# design.net
KiCad netlist of a schematic drawn in Altium Designer
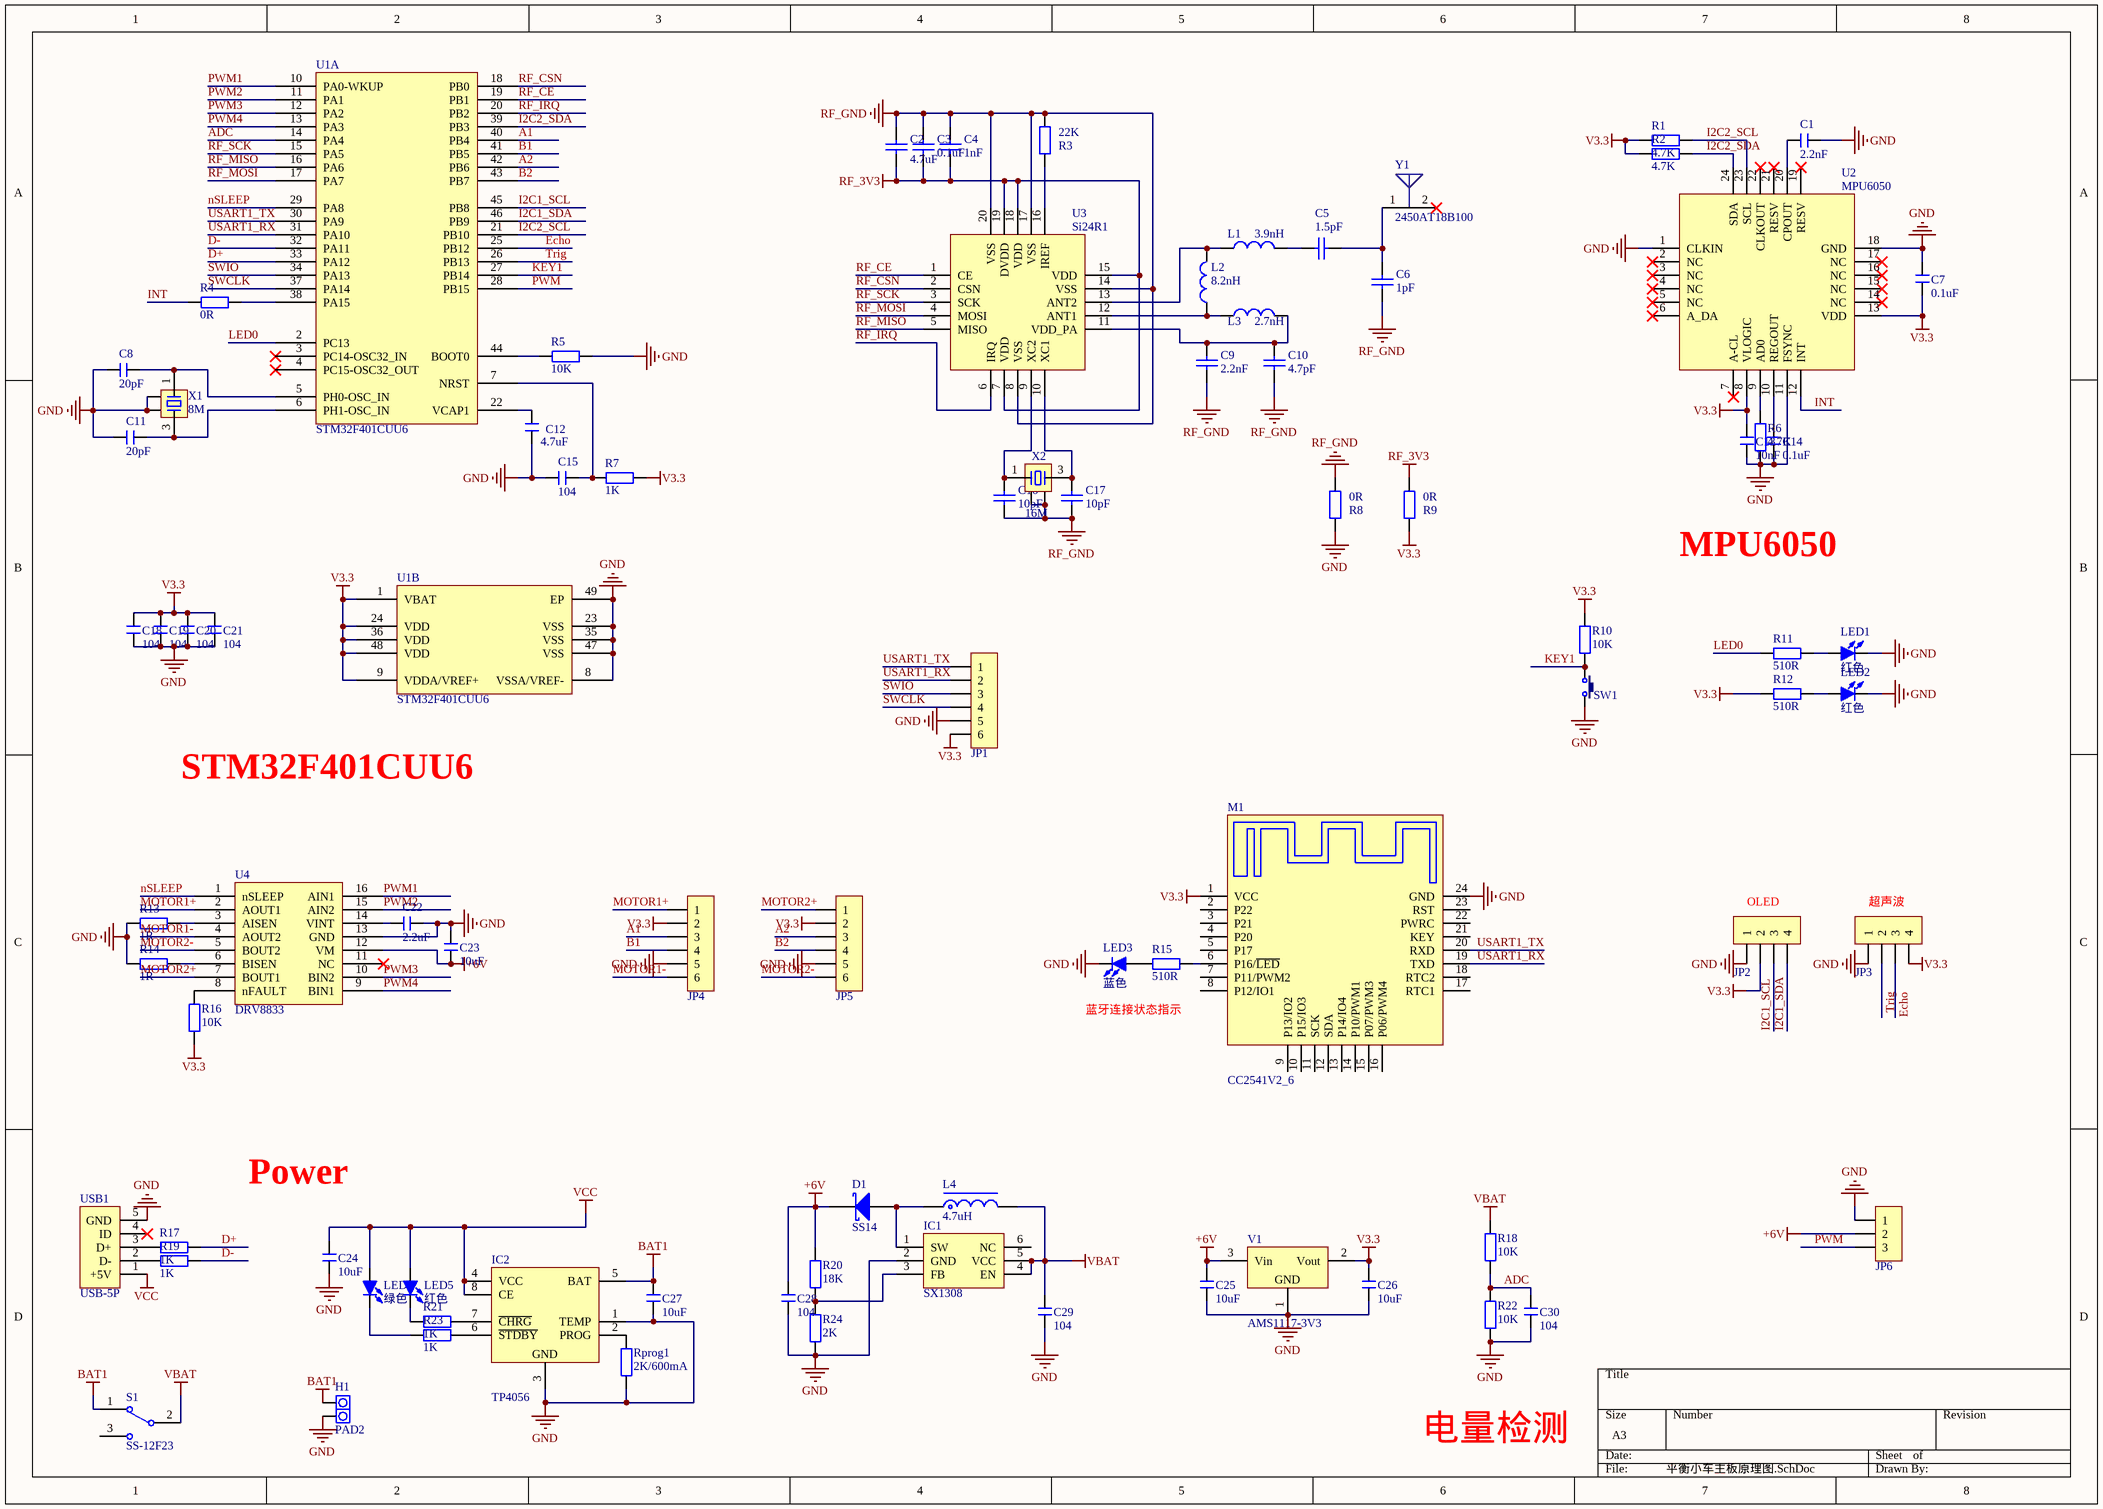
[diagram p0: 平衡小车主板原理图.SchDoc]

(export (version "E")
  (design (tool "Eeschema 10.0.6"))
  (components
    (comp (ref "C1")
      (value "2.2nF")
      (footprint "C 0603_L")
      (description "贴片电容")
      (libsource (lib "0.1 - 电阻-电容-电感") (part "C"))
    )
    (comp (ref "C2")
      (value "4.7uF")
      (footprint "C 0603_L")
      (fields (field (name "Comment") "C_0603") (field (name "PUBLISHER") "Altium Limited"))
      (libsource (lib "RoboFly") (part "C_0603"))
    )
    (comp (ref "C3")
      (value "0.1uF")
      (footprint "C 0603_L")
      (fields (field (name "Comment") "C_0603") (field (name "PUBLISHER") "Altium Limited"))
      (libsource (lib "RoboFly") (part "C_0603"))
    )
    (comp (ref "C4")
      (value "1nF")
      (footprint "C 0603_L")
      (fields (field (name "Comment") "C_0603") (field (name "PUBLISHER") "Altium Limited"))
      (libsource (lib "RoboFly") (part "C_0603"))
    )
    (comp (ref "C5")
      (value "1.5pF")
      (footprint "C 0603_L")
      (fields (field (name "Comment") "C_0603") (field (name "PUBLISHER") "Altium Limited"))
      (libsource (lib "RoboFly") (part "C_0603"))
    )
    (comp (ref "C6")
      (value "1pF")
      (footprint "C 0603_L")
      (fields (field (name "Comment") "C_0603") (field (name "PUBLISHER") "Altium Limited"))
      (libsource (lib "RoboFly") (part "C_0603"))
    )
    (comp (ref "C7")
      (value "0.1uF")
      (footprint "C 0603_L")
      (description "贴片电容")
      (libsource (lib "0.1 - 电阻-电容-电感") (part "C"))
    )
    (comp (ref "C8")
      (value "20pF")
      (footprint "R 0603_M")
      (description "贴片电容")
      (libsource (lib "0.1 - 电阻-电容-电感") (part "C"))
    )
    (comp (ref "C9")
      (value "2.2nF")
      (footprint "C 0603_L")
      (fields (field (name "Comment") "C_0603") (field (name "PUBLISHER") "Altium Limited"))
      (libsource (lib "RoboFly") (part "C_0603"))
    )
    (comp (ref "C10")
      (value "4.7pF")
      (footprint "C 0603_L")
      (fields (field (name "Comment") "C_0603") (field (name "PUBLISHER") "Altium Limited"))
      (libsource (lib "RoboFly") (part "C_0603"))
    )
    (comp (ref "C11")
      (value "20pF")
      (footprint "R 0603_M")
      (description "贴片电容")
      (libsource (lib "0.1 - 电阻-电容-电感") (part "C"))
    )
    (comp (ref "C12")
      (value "4.7uF")
      (footprint "C 0603_L")
      (description "贴片电容")
      (libsource (lib "0.1 - 电阻-电容-电感") (part "C"))
    )
    (comp (ref "C13")
      (value "10nF")
      (footprint "C 0603_L")
      (description "贴片电容")
      (libsource (lib "0.1 - 电阻-电容-电感") (part "C"))
    )
    (comp (ref "C14")
      (value "0.1uF")
      (footprint "C 0603_L")
      (description "贴片电容")
      (libsource (lib "0.1 - 电阻-电容-电感") (part "C"))
    )
    (comp (ref "C15")
      (value "104")
      (footprint "C 0603_L")
      (description "贴片电容")
      (libsource (lib "0.1 - 电阻-电容-电感") (part "C"))
    )
    (comp (ref "C16")
      (value "10pF")
      (footprint "C 0603_L")
      (fields (field (name "Comment") "C_0603") (field (name "PUBLISHER") "Altium Limited"))
      (libsource (lib "RoboFly") (part "C_0603"))
    )
    (comp (ref "C17")
      (value "10pF")
      (footprint "C 0603_L")
      (fields (field (name "Comment") "C_0603") (field (name "PUBLISHER") "Altium Limited"))
      (libsource (lib "RoboFly") (part "C_0603"))
    )
    (comp (ref "C18")
      (value "104")
      (footprint "C 0603_L")
      (description "贴片电容")
      (libsource (lib "0.1 - 电阻-电容-电感") (part "C"))
    )
    (comp (ref "C19")
      (value "104")
      (footprint "C 0603_L")
      (description "贴片电容")
      (libsource (lib "0.1 - 电阻-电容-电感") (part "C"))
    )
    (comp (ref "C20")
      (value "104")
      (footprint "C 0603_L")
      (description "贴片电容")
      (libsource (lib "0.1 - 电阻-电容-电感") (part "C"))
    )
    (comp (ref "C21")
      (value "104")
      (footprint "C 0603_L")
      (description "贴片电容")
      (libsource (lib "0.1 - 电阻-电容-电感") (part "C"))
    )
    (comp (ref "C22")
      (value "2.2uF")
      (footprint "C 0603_L")
      (description "贴片电容")
      (libsource (lib "0.1 - 电阻-电容-电感") (part "C"))
    )
    (comp (ref "C23")
      (value "10uF")
      (footprint "C 0603_L")
      (description "贴片电容")
      (libsource (lib "0.1 - 电阻-电容-电感") (part "C"))
    )
    (comp (ref "C24")
      (value "10uF")
      (footprint "C 0603_L")
      (description "贴片电容")
      (libsource (lib "0.1 - 电阻-电容-电感") (part "C"))
    )
    (comp (ref "C25")
      (value "10uF")
      (footprint "C 0603_L")
      (description "贴片电容")
      (libsource (lib "0.1 - 电阻-电容-电感") (part "C"))
    )
    (comp (ref "C26")
      (value "10uF")
      (footprint "C 0603_L")
      (description "贴片电容")
      (libsource (lib "0.1 - 电阻-电容-电感") (part "C"))
    )
    (comp (ref "C27")
      (value "10uF")
      (footprint "C 0603_L")
      (description "贴片电容")
      (libsource (lib "0.1 - 电阻-电容-电感") (part "C"))
    )
    (comp (ref "C28")
      (value "104")
      (footprint "C 0603_L")
      (description "贴片电容")
      (libsource (lib "0.1 - 电阻-电容-电感") (part "C"))
    )
    (comp (ref "C29")
      (value "104")
      (footprint "C 0603_L")
      (description "贴片电容")
      (libsource (lib "0.1 - 电阻-电容-电感") (part "C"))
    )
    (comp (ref "C30")
      (value "104")
      (footprint "C 0603_L")
      (description "贴片电容")
      (libsource (lib "0.1 - 电阻-电容-电感") (part "C"))
    )
    (comp (ref "D1")
      (value "SS14")
      (footprint "SMA")
      (description "肖特基二极管")
      (libsource (lib "0.2 -  二极管-整流桥") (part "SS14"))
    )
    (comp (ref "H1")
      (value "PAD2")
      (footprint "PAD2-2.54")
      (description "引线焊盘")
      (fields (field (name "版权归属") "封装库来自淘宝 ID：黄晶宝石"))
      (libsource (lib "4.1 - 未分类器件") (part "PAD2"))
    )
    (comp (ref "IC1")
      (value "SX1308")
      (footprint "SOT23-6N")
      (description "可调升压芯片")
      (fields (field (name "版权归属") "封装库来自淘宝 ID：黄晶宝石"))
      (libsource (lib "1.1 - 电源类芯片") (part "SX1308"))
    )
    (comp (ref "IC2")
      (value "TP4056")
      (footprint "SOP8_N")
      (description "锂电池充电管理")
      (libsource (lib "1.1 - 电源类芯片") (part "TP4056"))
    )
    (comp (ref "JP1")
      (value "HDR-1X6")
      (footprint "SH1.0-6P")
      (description "6P接插件")
      (fields (field (name "版权归属") "封装库来自淘宝 ID：黄晶宝石"))
      (libsource (lib "5.3 - 接插件-脚距2.54 (100mil) ") (part "Header 6"))
    )
    (comp (ref "JP2")
      (value "HDR-1X4")
      (footprint "HDR2.54-M-LI-4P")
      (description "4P接插件")
      (fields (field (name "版权归属") "封装库来自淘宝 ID：黄晶宝石"))
      (libsource (lib "5.3 - 接插件-脚距2.54 (100mil) ") (part "Header 4"))
    )
    (comp (ref "JP3")
      (value "HDR-1X4")
      (footprint "HDR2.54-M-LI-4P")
      (description "4P接插件")
      (fields (field (name "版权归属") "封装库来自淘宝 ID：黄晶宝石"))
      (libsource (lib "5.3 - 接插件-脚距2.54 (100mil) ") (part "Header 4"))
    )
    (comp (ref "JP4")
      (value "HDR-1X6")
      (footprint "SH1.0-6P")
      (description "6P接插件")
      (fields (field (name "版权归属") "封装库来自淘宝 ID：黄晶宝石"))
      (libsource (lib "5.3 - 接插件-脚距2.54 (100mil) ") (part "Header 6"))
    )
    (comp (ref "JP5")
      (value "HDR-1X6")
      (footprint "SH1.0-6P")
      (description "6P接插件")
      (fields (field (name "版权归属") "封装库来自淘宝 ID：黄晶宝石"))
      (libsource (lib "5.3 - 接插件-脚距2.54 (100mil) ") (part "Header 6"))
    )
    (comp (ref "JP6")
      (value "HDR-1X3")
      (footprint "HDR2.54-LI-3P")
      (description "3P接插件")
      (fields (field (name "版权归属") "封装库来自淘宝 ID：黄晶宝石"))
      (libsource (lib "5.3 - 接插件-脚距2.54 (100mil) ") (part "Header 3"))
    )
    (comp (ref "L1")
      (value "3.9nH")
      (footprint "L 0603")
      (description "电感")
      (fields (field (name "Comment") "Inductor") (field (name "PUBLISHER") "Altium Limited"))
      (libsource (lib "RoboFly") (part "Inductor_1"))
    )
    (comp (ref "L2")
      (value "8.2nH")
      (footprint "L 0603")
      (description "电感")
      (fields (field (name "Comment") "Inductor") (field (name "PUBLISHER") "Altium Limited"))
      (libsource (lib "RoboFly") (part "Inductor_1"))
    )
    (comp (ref "L3")
      (value "2.7nH")
      (footprint "L 0603")
      (description "电感")
      (fields (field (name "Comment") "Inductor") (field (name "PUBLISHER") "Altium Limited"))
      (libsource (lib "RoboFly") (part "Inductor_1"))
    )
    (comp (ref "L4")
      (value "4.7uH")
      (footprint "NR4020")
      (description "NR磁胶电感")
      (fields (field (name "版权归属") "来自淘宝 ID：黄晶宝石"))
      (libsource (lib "0.1 - 电阻-电容-电感") (part "L-NR"))
    )
    (comp (ref "LED1")
      (value "红色")
      (footprint "LED 0603R")
      (description "贴片LED")
      (fields (field (name "版权归属") "封装库来自淘宝 ID：黄晶宝石"))
      (libsource (lib "0.3 - LED发光二极管") (part "LED-SMD"))
    )
    (comp (ref "LED2")
      (value "红色")
      (footprint "LED 0603R")
      (description "贴片LED")
      (fields (field (name "版权归属") "封装库来自淘宝 ID：黄晶宝石"))
      (libsource (lib "0.3 - LED发光二极管") (part "LED-SMD"))
    )
    (comp (ref "LED3")
      (value "蓝色")
      (footprint "LED 0603B")
      (description "贴片LED")
      (fields (field (name "版权归属") "封装库来自淘宝 ID：黄晶宝石"))
      (libsource (lib "0.3 - LED发光二极管") (part "LED-SMD"))
    )
    (comp (ref "LED4")
      (value "绿色")
      (footprint "LED 0603G")
      (description "贴片LED")
      (fields (field (name "版权归属") "封装库来自淘宝 ID：黄晶宝石"))
      (libsource (lib "0.3 - LED发光二极管") (part "LED-SMD"))
    )
    (comp (ref "LED5")
      (value "红色")
      (footprint "LED 0603R")
      (description "贴片LED")
      (fields (field (name "版权归属") "封装库来自淘宝 ID：黄晶宝石"))
      (libsource (lib "0.3 - LED发光二极管") (part "LED-SMD"))
    )
    (comp (ref "M1")
      (value "CC2541V2_6")
      (footprint "CC2541V2_6")
      (description "蓝牙4.0透传模块")
      (fields (field (name "版权归属") "封装库来自淘宝 ID：黄晶宝石"))
      (libsource (lib "0.9 - 模块") (part "CC2541V2_6"))
    )
    (comp (ref "R1")
      (value "4.7K")
      (footprint "R 0603_L")
      (description "贴片电阻")
      (fields (field (name "版权归属") "来自淘宝 ID：黄晶宝石"))
      (libsource (lib "0.1 - 电阻-电容-电感") (part "R"))
    )
    (comp (ref "R2")
      (value "4.7K")
      (footprint "R 0603_L")
      (description "贴片电阻")
      (fields (field (name "版权归属") "来自淘宝 ID：黄晶宝石"))
      (libsource (lib "0.1 - 电阻-电容-电感") (part "R"))
    )
    (comp (ref "R3")
      (value "22K")
      (footprint "R 0603_L")
      (fields (field (name "Comment") "R_0603") (field (name "PUBLISHER") "Altium Limited"))
      (libsource (lib "RoboFly") (part "R_0603"))
    )
    (comp (ref "R4")
      (value "0R")
      (footprint "R 0603_L")
      (description "贴片电阻")
      (fields (field (name "版权归属") "来自淘宝 ID：黄晶宝石"))
      (libsource (lib "0.1 - 电阻-电容-电感") (part "R"))
    )
    (comp (ref "R5")
      (value "10K")
      (footprint "R 0603_L")
      (description "贴片电阻")
      (fields (field (name "版权归属") "来自淘宝 ID：黄晶宝石"))
      (libsource (lib "0.1 - 电阻-电容-电感") (part "R"))
    )
    (comp (ref "R6")
      (value "4.7K")
      (footprint "R 0603_L")
      (description "贴片电阻")
      (fields (field (name "版权归属") "来自淘宝 ID：黄晶宝石"))
      (libsource (lib "0.1 - 电阻-电容-电感") (part "R"))
    )
    (comp (ref "R7")
      (value "1K")
      (footprint "R 0603_L")
      (description "贴片电阻")
      (fields (field (name "版权归属") "来自淘宝 ID：黄晶宝石"))
      (libsource (lib "0.1 - 电阻-电容-电感") (part "R"))
    )
    (comp (ref "R8")
      (value "0R")
      (footprint "R 0603_L")
      (fields (field (name "Comment") "R_0603") (field (name "PUBLISHER") "Altium Limited"))
      (libsource (lib "RoboFly") (part "R_0603"))
    )
    (comp (ref "R9")
      (value "0R")
      (footprint "R 0603_L")
      (fields (field (name "Comment") "R_0603") (field (name "PUBLISHER") "Altium Limited"))
      (libsource (lib "RoboFly") (part "R_0603"))
    )
    (comp (ref "R10")
      (value "10K")
      (footprint "R 0603_L")
      (description "贴片电阻")
      (fields (field (name "版权归属") "来自淘宝 ID：黄晶宝石"))
      (libsource (lib "0.1 - 电阻-电容-电感") (part "R"))
    )
    (comp (ref "R11")
      (value "510R")
      (footprint "R 0603_L")
      (description "贴片电阻")
      (fields (field (name "版权归属") "来自淘宝 ID：黄晶宝石"))
      (libsource (lib "0.1 - 电阻-电容-电感") (part "R"))
    )
    (comp (ref "R12")
      (value "510R")
      (footprint "R 0603_L")
      (description "贴片电阻")
      (fields (field (name "版权归属") "来自淘宝 ID：黄晶宝石"))
      (libsource (lib "0.1 - 电阻-电容-电感") (part "R"))
    )
    (comp (ref "R13")
      (value "1R")
      (footprint "R 0603_L")
      (description "贴片电阻")
      (fields (field (name "版权归属") "来自淘宝 ID：黄晶宝石"))
      (libsource (lib "0.1 - 电阻-电容-电感") (part "R"))
    )
    (comp (ref "R14")
      (value "1R")
      (footprint "R 0603_L")
      (description "贴片电阻")
      (fields (field (name "版权归属") "来自淘宝 ID：黄晶宝石"))
      (libsource (lib "0.1 - 电阻-电容-电感") (part "R"))
    )
    (comp (ref "R15")
      (value "510R")
      (footprint "R 0603_L")
      (description "贴片电阻")
      (fields (field (name "版权归属") "来自淘宝 ID：黄晶宝石"))
      (libsource (lib "0.1 - 电阻-电容-电感") (part "R"))
    )
    (comp (ref "R16")
      (value "10K")
      (footprint "R 0603_L")
      (description "贴片电阻")
      (fields (field (name "版权归属") "来自淘宝 ID：黄晶宝石"))
      (libsource (lib "0.1 - 电阻-电容-电感") (part "R"))
    )
    (comp (ref "R17")
      (value "1K")
      (footprint "R 0603_L")
      (description "贴片电阻")
      (fields (field (name "版权归属") "来自淘宝 ID：黄晶宝石"))
      (libsource (lib "0.1 - 电阻-电容-电感") (part "R"))
    )
    (comp (ref "R18")
      (value "10K")
      (footprint "R 0603_L")
      (description "贴片电阻")
      (fields (field (name "版权归属") "来自淘宝 ID：黄晶宝石"))
      (libsource (lib "0.1 - 电阻-电容-电感") (part "R"))
    )
    (comp (ref "R19")
      (value "1K")
      (footprint "R 0603_L")
      (description "贴片电阻")
      (fields (field (name "版权归属") "来自淘宝 ID：黄晶宝石"))
      (libsource (lib "0.1 - 电阻-电容-电感") (part "R"))
    )
    (comp (ref "R20")
      (value "18K")
      (footprint "R 0603_L")
      (description "贴片电阻")
      (fields (field (name "版权归属") "来自淘宝 ID：黄晶宝石"))
      (libsource (lib "0.1 - 电阻-电容-电感") (part "R"))
    )
    (comp (ref "R21")
      (value "1K")
      (footprint "R 0603_L")
      (description "贴片电阻")
      (fields (field (name "版权归属") "来自淘宝 ID：黄晶宝石"))
      (libsource (lib "0.1 - 电阻-电容-电感") (part "R"))
    )
    (comp (ref "R22")
      (value "10K")
      (footprint "R 0603_L")
      (description "贴片电阻")
      (fields (field (name "版权归属") "来自淘宝 ID：黄晶宝石"))
      (libsource (lib "0.1 - 电阻-电容-电感") (part "R"))
    )
    (comp (ref "R23")
      (value "1K")
      (footprint "R 0603_L")
      (description "贴片电阻")
      (fields (field (name "版权归属") "来自淘宝 ID：黄晶宝石"))
      (libsource (lib "0.1 - 电阻-电容-电感") (part "R"))
    )
    (comp (ref "R24")
      (value "2K")
      (footprint "R 0603_L")
      (description "贴片电阻")
      (fields (field (name "版权归属") "来自淘宝 ID：黄晶宝石"))
      (libsource (lib "0.1 - 电阻-电容-电感") (part "R"))
    )
    (comp (ref "Rprog1")
      (value "2K/600mA")
      (footprint "R 0603_M")
      (description "贴片电阻")
      (fields (field (name "版权归属") "来自淘宝 ID：黄晶宝石"))
      (libsource (lib "0.1 - 电阻-电容-电感") (part "R"))
    )
    (comp (ref "S1")
      (value "SS-12F23")
      (footprint "SWITCH_PWR")
      (description "1路波动开关")
      (fields (field (name "版权归属") "封装库来自淘宝 ID：黄晶宝石"))
      (libsource (lib "0.7 - 常用按键-开关") (part "SSW-1P"))
    )
    (comp (ref "SW1")
      (value "3x6x5")
      (footprint "TSW SMD-3*6*2.5")
      (description "3x6轻触开关")
      (fields (field (name "版权归属") "封装库来自淘宝 ID：黄晶宝石"))
      (libsource (lib "0.7 - 常用按键-开关") (part "TSW 3x6"))
    )
    (comp (ref "U1")
      (value "STM32F401CUU6")
      (footprint "QFN48 7X7_M")
      (libsource (lib "Schlib1") (part "STM32F401CUU6"))
    )
    (comp (ref "U2") (value "MPU6050") (footprint "QFN24 4x4_M") (libsource (lib "RoboFly") (part "MPU6050")))
    (comp (ref "U3") (value "Si24R1") (footprint "QFN20 4x4_M") (libsource (lib "RoboFly") (part "nRF24L01")))
    (comp (ref "U4")
      (value "DRV8833")
      (footprint "TSSOP-16")
      (description "DRV8833电机驱动芯片2.7v-10.8v")
      (libsource (lib "原理图库") (part "DRV8833"))
    )
    (comp (ref "USB1")
      (value "USB-5P")
      (footprint "USB-MICRO_D")
      (description "微型USB母座")
      (libsource (lib "0.8 - 网口-音频插座") (part "USB-5P"))
    )
    (comp (ref "V1")
      (value "AMS1117-3V3")
      (footprint "SOT223_L")
      (description "三端稳压芯片")
      (libsource (lib "1.1 - 电源类芯片") (part "AMS1117"))
    )
    (comp (ref "X1")
      (value "8M")
      (footprint "OSC 3225-4P")
      (description "4脚无源晶振")
      (fields (field (name "版权归属") "源创客"))
      (libsource (lib "") (part "XTAL-4P_1"))
    )
    (comp (ref "X2")
      (value "16M")
      (footprint "OSC 3225-4P")
      (description "4脚无源晶振")
      (fields (field (name "版权归属") "源创客"))
      (libsource (lib "2.0 - 保险丝-晶振-光耦") (part "XTAL-4P"))
    )
    (comp (ref "Y1")
      (value "2450AT18B100")
      (footprint "1206")
      (libsource (lib "MiniFly ") (part "CHIP_ANTENNA"))
    )
  )
  (nets
    (net (code "1") (name "+6V") (class "Default")
      (node (ref "C23") (pin "1") (pinfunction "1_1") (pintype "passive"))
      (node (ref "C25") (pin "2") (pinfunction "2_2") (pintype "passive"))
      (node (ref "C28") (pin "2") (pinfunction "2_2") (pintype "passive"))
      (node (ref "D1") (pin "2") (pinfunction "K_2") (pintype "passive"))
      (node (ref "JP6") (pin "2") (pinfunction "2_2") (pintype "passive"))
      (node (ref "R20") (pin "2") (pinfunction "2_2") (pintype "passive"))
      (node (ref "U4") (pin "12") (pinfunction "VM_12") (pintype "passive"))
      (node (ref "V1") (pin "3") (pinfunction "Vin_3") (pintype "passive"))
    )
    (net (code "2") (name "/A1") (class "Default")
      (node (ref "JP4") (pin "3") (pinfunction "3_3") (pintype "passive"))
      (node (ref "U1") (pin "40") (pinfunction "PB4_40") (pintype "passive"))
    )
    (net (code "3") (name "/A2") (class "Default")
      (node (ref "JP5") (pin "3") (pinfunction "3_3") (pintype "passive"))
      (node (ref "U1") (pin "42") (pinfunction "PB6_42") (pintype "passive"))
    )
    (net (code "4") (name "/ADC") (class "Default")
      (node (ref "C30") (pin "2") (pinfunction "2_2") (pintype "passive"))
      (node (ref "R18") (pin "1") (pinfunction "1_1") (pintype "passive"))
      (node (ref "R22") (pin "2") (pinfunction "2_2") (pintype "passive"))
      (node (ref "U1") (pin "14") (pinfunction "PA4_14") (pintype "passive"))
    )
    (net (code "5") (name "/B1") (class "Default")
      (node (ref "JP4") (pin "4") (pinfunction "4_4") (pintype "passive"))
      (node (ref "U1") (pin "41") (pinfunction "PB5_41") (pintype "passive"))
    )
    (net (code "6") (name "/B2") (class "Default")
      (node (ref "JP5") (pin "4") (pinfunction "4_4") (pintype "passive"))
      (node (ref "U1") (pin "43") (pinfunction "PB7_43") (pintype "passive"))
    )
    (net (code "7") (name "/D+") (class "Default")
      (node (ref "R17") (pin "2") (pinfunction "2_2") (pintype "passive"))
      (node (ref "U1") (pin "33") (pinfunction "PA12_33") (pintype "passive"))
    )
    (net (code "8") (name "/D-") (class "Default")
      (node (ref "R19") (pin "2") (pinfunction "2_2") (pintype "passive"))
      (node (ref "U1") (pin "32") (pinfunction "PA11_32") (pintype "passive"))
    )
    (net (code "9") (name "/Echo") (class "Default")
      (node (ref "JP3") (pin "3") (pinfunction "3_3") (pintype "passive"))
      (node (ref "U1") (pin "25") (pinfunction "PB12_25") (pintype "passive"))
    )
    (net (code "10") (name "/I2C1_SCL") (class "Default")
      (node (ref "JP2") (pin "3") (pinfunction "3_3") (pintype "passive"))
      (node (ref "U1") (pin "45") (pinfunction "PB8_45") (pintype "passive"))
    )
    (net (code "11") (name "/I2C1_SDA") (class "Default")
      (node (ref "JP2") (pin "4") (pinfunction "4_4") (pintype "passive"))
      (node (ref "U1") (pin "46") (pinfunction "PB9_46") (pintype "passive"))
    )
    (net (code "12") (name "/I2C2_SCL") (class "Default")
      (node (ref "R1") (pin "1") (pinfunction "1_1") (pintype "passive"))
      (node (ref "U1") (pin "21") (pinfunction "PB10_21") (pintype "passive"))
      (node (ref "U2") (pin "23") (pinfunction "SCL_23") (pintype "passive"))
    )
    (net (code "13") (name "/I2C2_SDA") (class "Default")
      (node (ref "R2") (pin "1") (pinfunction "1_1") (pintype "passive"))
      (node (ref "U1") (pin "39") (pinfunction "PB3_39") (pintype "passive"))
      (node (ref "U2") (pin "24") (pinfunction "SDA_24") (pintype "passive"))
    )
    (net (code "14") (name "/INT") (class "Default")
      (node (ref "R4") (pin "1") (pinfunction "1_1") (pintype "passive"))
      (node (ref "U2") (pin "12") (pinfunction "INT_12") (pintype "passive"))
    )
    (net (code "15") (name "/KEY1") (class "Default")
      (node (ref "R10") (pin "2") (pinfunction "2_2") (pintype "passive"))
      (node (ref "SW1") (pin "1") (pinfunction "1_1") (pintype "passive"))
      (node (ref "U1") (pin "27") (pinfunction "PB14_27") (pintype "passive"))
    )
    (net (code "16") (name "/LED0") (class "Default")
      (node (ref "R11") (pin "2") (pinfunction "2_2") (pintype "passive"))
      (node (ref "U1") (pin "2") (pinfunction "PC13_2") (pintype "passive"))
    )
    (net (code "17") (name "/MOTOR1+") (class "Default")
      (node (ref "JP4") (pin "1") (pinfunction "1_1") (pintype "passive"))
      (node (ref "U4") (pin "2") (pinfunction "AOUT1_2") (pintype "passive"))
    )
    (net (code "18") (name "/MOTOR1-") (class "Default")
      (node (ref "JP4") (pin "6") (pinfunction "6_6") (pintype "passive"))
      (node (ref "U4") (pin "4") (pinfunction "AOUT2_4") (pintype "passive"))
    )
    (net (code "19") (name "/MOTOR2+") (class "Default")
      (node (ref "JP5") (pin "1") (pinfunction "1_1") (pintype "passive"))
      (node (ref "U4") (pin "7") (pinfunction "BOUT1_7") (pintype "passive"))
    )
    (net (code "20") (name "/MOTOR2-") (class "Default")
      (node (ref "JP5") (pin "6") (pinfunction "6_6") (pintype "passive"))
      (node (ref "U4") (pin "5") (pinfunction "BOUT2_5") (pintype "passive"))
    )
    (net (code "21") (name "/PWM") (class "Default")
      (node (ref "JP6") (pin "3") (pinfunction "3_3") (pintype "passive"))
      (node (ref "U1") (pin "28") (pinfunction "PB15_28") (pintype "passive"))
    )
    (net (code "22") (name "/PWM1") (class "Default")
      (node (ref "U1") (pin "10") (pinfunction "PA0-WKUP_10") (pintype "passive"))
      (node (ref "U4") (pin "16") (pinfunction "AIN1_16") (pintype "passive"))
    )
    (net (code "23") (name "/PWM2") (class "Default")
      (node (ref "U1") (pin "11") (pinfunction "PA1_11") (pintype "passive"))
      (node (ref "U4") (pin "15") (pinfunction "AIN2_15") (pintype "passive"))
    )
    (net (code "24") (name "/PWM3") (class "Default")
      (node (ref "U1") (pin "12") (pinfunction "PA2_12") (pintype "passive"))
      (node (ref "U4") (pin "10") (pinfunction "BIN2_10") (pintype "passive"))
    )
    (net (code "25") (name "/PWM4") (class "Default")
      (node (ref "U1") (pin "13") (pinfunction "PA3_13") (pintype "passive"))
      (node (ref "U4") (pin "9") (pinfunction "BIN1_9") (pintype "passive"))
    )
    (net (code "26") (name "/RF_CE") (class "Default")
      (node (ref "U1") (pin "19") (pinfunction "PB1_19") (pintype "passive"))
      (node (ref "U3") (pin "1") (pinfunction "CE_1") (pintype "passive"))
    )
    (net (code "27") (name "/RF_CSN") (class "Default")
      (node (ref "U1") (pin "18") (pinfunction "PB0_18") (pintype "passive"))
      (node (ref "U3") (pin "2") (pinfunction "CSN_2") (pintype "passive"))
    )
    (net (code "28") (name "/RF_IRQ") (class "Default")
      (node (ref "U1") (pin "20") (pinfunction "PB2_20") (pintype "passive"))
      (node (ref "U3") (pin "6") (pinfunction "IRQ_6") (pintype "passive"))
    )
    (net (code "29") (name "/RF_MISO") (class "Default")
      (node (ref "U1") (pin "16") (pinfunction "PA6_16") (pintype "passive"))
      (node (ref "U3") (pin "5") (pinfunction "MISO_5") (pintype "passive"))
    )
    (net (code "30") (name "/RF_MOSI") (class "Default")
      (node (ref "U1") (pin "17") (pinfunction "PA7_17") (pintype "passive"))
      (node (ref "U3") (pin "4") (pinfunction "MOSI_4") (pintype "passive"))
    )
    (net (code "31") (name "/RF_SCK") (class "Default")
      (node (ref "U1") (pin "15") (pinfunction "PA5_15") (pintype "passive"))
      (node (ref "U3") (pin "3") (pinfunction "SCK_3") (pintype "passive"))
    )
    (net (code "32") (name "/SWCLK") (class "Default")
      (node (ref "JP1") (pin "4") (pinfunction "4_4") (pintype "passive"))
      (node (ref "U1") (pin "37") (pinfunction "PA14_37") (pintype "passive"))
    )
    (net (code "33") (name "/SWIO") (class "Default")
      (node (ref "JP1") (pin "3") (pinfunction "3_3") (pintype "passive"))
      (node (ref "U1") (pin "34") (pinfunction "PA13_34") (pintype "passive"))
    )
    (net (code "34") (name "/Trig") (class "Default")
      (node (ref "JP3") (pin "2") (pinfunction "2_2") (pintype "passive"))
      (node (ref "U1") (pin "26") (pinfunction "PB13_26") (pintype "passive"))
    )
    (net (code "35") (name "/USART1_RX") (class "Default")
      (node (ref "JP1") (pin "2") (pinfunction "2_2") (pintype "passive"))
      (node (ref "M1") (pin "19") (pinfunction "TXD_19") (pintype "passive"))
      (node (ref "U1") (pin "31") (pinfunction "PA10_31") (pintype "passive"))
    )
    (net (code "36") (name "/USART1_TX") (class "Default")
      (node (ref "JP1") (pin "1") (pinfunction "1_1") (pintype "passive"))
      (node (ref "M1") (pin "20") (pinfunction "RXD_20") (pintype "passive"))
      (node (ref "U1") (pin "30") (pinfunction "PA9_30") (pintype "passive"))
    )
    (net (code "37") (name "/nSLEEP") (class "Default")
      (node (ref "U1") (pin "29") (pinfunction "PA8_29") (pintype "passive"))
      (node (ref "U4") (pin "1") (pinfunction "nSLEEP_1") (pintype "passive"))
    )
    (net (code "38") (name "BAT1") (class "Default")
      (node (ref "C27") (pin "2") (pinfunction "2_2") (pintype "passive"))
      (node (ref "H1") (pin "1") (pinfunction "1_1") (pintype "passive"))
      (node (ref "IC2") (pin "5") (pinfunction "BAT_5") (pintype "passive"))
      (node (ref "S1") (pin "1") (pinfunction "1_1") (pintype "passive"))
    )
    (net (code "39") (name "GND") (class "Default")
      (node (ref "C1") (pin "1") (pinfunction "1_1") (pintype "passive"))
      (node (ref "C11") (pin "2") (pinfunction "2_2") (pintype "passive"))
      (node (ref "C12") (pin "2") (pinfunction "2_2") (pintype "passive"))
      (node (ref "C13") (pin "1") (pinfunction "1_1") (pintype "passive"))
      (node (ref "C14") (pin "1") (pinfunction "1_1") (pintype "passive"))
      (node (ref "C15") (pin "1") (pinfunction "1_1") (pintype "passive"))
      (node (ref "C18") (pin "1") (pinfunction "1_1") (pintype "passive"))
      (node (ref "C19") (pin "1") (pinfunction "1_1") (pintype "passive"))
      (node (ref "C20") (pin "1") (pinfunction "1_1") (pintype "passive"))
      (node (ref "C21") (pin "1") (pinfunction "1_1") (pintype "passive"))
      (node (ref "C22") (pin "1") (pinfunction "1_1") (pintype "passive"))
      (node (ref "C23") (pin "2") (pinfunction "2_2") (pintype "passive"))
      (node (ref "C24") (pin "1") (pinfunction "1_1") (pintype "passive"))
      (node (ref "C25") (pin "1") (pinfunction "1_1") (pintype "passive"))
      (node (ref "C26") (pin "1") (pinfunction "1_1") (pintype "passive"))
      (node (ref "C27") (pin "1") (pinfunction "1_1") (pintype "passive"))
      (node (ref "C28") (pin "1") (pinfunction "1_1") (pintype "passive"))
      (node (ref "C29") (pin "1") (pinfunction "1_1") (pintype "passive"))
      (node (ref "C30") (pin "1") (pinfunction "1_1") (pintype "passive"))
      (node (ref "C7") (pin "2") (pinfunction "2_2") (pintype "passive"))
      (node (ref "C8") (pin "2") (pinfunction "2_2") (pintype "passive"))
      (node (ref "H1") (pin "2") (pinfunction "2_2") (pintype "passive"))
      (node (ref "IC1") (pin "2") (pinfunction "GND_2") (pintype "passive"))
      (node (ref "IC2") (pin "1") (pinfunction "TEMP_1") (pintype "passive"))
      (node (ref "IC2") (pin "3") (pinfunction "GND_3") (pintype "passive"))
      (node (ref "JP1") (pin "5") (pinfunction "5_5") (pintype "passive"))
      (node (ref "JP2") (pin "1") (pinfunction "1_1") (pintype "passive"))
      (node (ref "JP3") (pin "1") (pinfunction "1_1") (pintype "passive"))
      (node (ref "JP4") (pin "5") (pinfunction "5_5") (pintype "passive"))
      (node (ref "JP5") (pin "5") (pinfunction "5_5") (pintype "passive"))
      (node (ref "JP6") (pin "1") (pinfunction "1_1") (pintype "passive"))
      (node (ref "LED1") (pin "2") (pinfunction "K_2") (pintype "passive"))
      (node (ref "LED2") (pin "2") (pinfunction "K_2") (pintype "passive"))
      (node (ref "LED3") (pin "2") (pinfunction "K_2") (pintype "passive"))
      (node (ref "M1") (pin "24") (pinfunction "GND_24") (pintype "passive"))
      (node (ref "R13") (pin "2") (pinfunction "2_2") (pintype "passive"))
      (node (ref "R14") (pin "2") (pinfunction "2_2") (pintype "passive"))
      (node (ref "R22") (pin "1") (pinfunction "1_1") (pintype "passive"))
      (node (ref "R24") (pin "1") (pinfunction "1_1") (pintype "passive"))
      (node (ref "R5") (pin "1") (pinfunction "1_1") (pintype "passive"))
      (node (ref "R6") (pin "2") (pinfunction "2_2") (pintype "passive"))
      (node (ref "R8") (pin "1") (pinfunction "1_1") (pintype "passive"))
      (node (ref "Rprog1") (pin "1") (pinfunction "1_1") (pintype "passive"))
      (node (ref "SW1") (pin "2") (pinfunction "2_2") (pintype "passive"))
      (node (ref "U1") (pin "23") (pinfunction "VSS_23") (pintype "passive"))
      (node (ref "U1") (pin "35") (pinfunction "VSS_35") (pintype "passive"))
      (node (ref "U1") (pin "47") (pinfunction "VSS_47") (pintype "passive"))
      (node (ref "U1") (pin "49") (pinfunction "EP_49") (pintype "passive"))
      (node (ref "U1") (pin "8") (pinfunction "VSSA/VREF-_8") (pintype "passive"))
      (node (ref "U2") (pin "1") (pinfunction "CLKIN_1") (pintype "passive"))
      (node (ref "U2") (pin "11") (pinfunction "FSYNC_11") (pintype "passive"))
      (node (ref "U2") (pin "18") (pinfunction "GND_18") (pintype "passive"))
      (node (ref "U4") (pin "13") (pinfunction "GND_13") (pintype "passive"))
      (node (ref "USB1") (pin "5") (pinfunction "GND_5") (pintype "passive"))
      (node (ref "V1") (pin "1") (pinfunction "GND_1") (pintype "passive"))
      (node (ref "X1") (pin "2") (pinfunction "2_2") (pintype "passive"))
      (node (ref "X1") (pin "4") (pinfunction "4_4") (pintype "passive"))
    )
    (net (code "40") (name "Net-(C5-Pad1)") (class "Default")
      (node (ref "C5") (pin "1") (pinfunction "1_1") (pintype "passive"))
      (node (ref "L1") (pin "2") (pinfunction "2_2") (pintype "passive"))
    )
    (net (code "41") (name "Net-(D1-A)") (class "Default")
      (node (ref "D1") (pin "1") (pinfunction "A_1") (pintype "passive"))
      (node (ref "IC1") (pin "1") (pinfunction "SW_1") (pintype "passive"))
      (node (ref "L4") (pin "1") (pinfunction "1_1") (pintype "passive"))
    )
    (net (code "42") (name "Net-(IC1-FB)") (class "Default")
      (node (ref "IC1") (pin "3") (pinfunction "FB_3") (pintype "passive"))
      (node (ref "R20") (pin "1") (pinfunction "1_1") (pintype "passive"))
      (node (ref "R24") (pin "2") (pinfunction "2_2") (pintype "passive"))
    )
    (net (code "43") (name "Net-(IC2-PROG)") (class "Default")
      (node (ref "IC2") (pin "2") (pinfunction "PROG_2") (pintype "passive"))
      (node (ref "Rprog1") (pin "2") (pinfunction "2_2") (pintype "passive"))
    )
    (net (code "44") (name "Net-(IC2-~{CHRG})") (class "Default")
      (node (ref "IC2") (pin "7") (pinfunction "~{CHRG}_7") (pintype "passive"))
      (node (ref "R21") (pin "1") (pinfunction "1_1") (pintype "passive"))
    )
    (net (code "45") (name "Net-(IC2-~{STDBY})") (class "Default")
      (node (ref "IC2") (pin "6") (pinfunction "~{STDBY}_6") (pintype "passive"))
      (node (ref "R23") (pin "2") (pinfunction "2_2") (pintype "passive"))
    )
    (net (code "46") (name "Net-(LED1-A)") (class "Default")
      (node (ref "LED1") (pin "1") (pinfunction "A_1") (pintype "passive"))
      (node (ref "R11") (pin "1") (pinfunction "1_1") (pintype "passive"))
    )
    (net (code "47") (name "Net-(LED2-A)") (class "Default")
      (node (ref "LED2") (pin "1") (pinfunction "A_1") (pintype "passive"))
      (node (ref "R12") (pin "1") (pinfunction "1_1") (pintype "passive"))
    )
    (net (code "48") (name "Net-(LED3-A)") (class "Default")
      (node (ref "LED3") (pin "1") (pinfunction "A_1") (pintype "passive"))
      (node (ref "R15") (pin "2") (pinfunction "2_2") (pintype "passive"))
    )
    (net (code "49") (name "Net-(LED4-K)") (class "Default")
      (node (ref "LED4") (pin "2") (pinfunction "K_2") (pintype "passive"))
      (node (ref "R23") (pin "1") (pinfunction "1_1") (pintype "passive"))
    )
    (net (code "50") (name "Net-(LED5-K)") (class "Default")
      (node (ref "LED5") (pin "2") (pinfunction "K_2") (pintype "passive"))
      (node (ref "R21") (pin "2") (pinfunction "2_2") (pintype "passive"))
    )
    (net (code "51") (name "Net-(M1-P16{slash}~{LED})") (class "Default")
      (node (ref "M1") (pin "6") (pinfunction "P16/~{LED}_6") (pintype "passive"))
      (node (ref "R15") (pin "1") (pinfunction "1_1") (pintype "passive"))
    )
    (net (code "52") (name "Net-(U1A-BOOT0)") (class "Default")
      (node (ref "R5") (pin "2") (pinfunction "2_2") (pintype "passive"))
      (node (ref "U1") (pin "44") (pinfunction "BOOT0_44") (pintype "passive"))
    )
    (net (code "53") (name "Net-(U1A-NRST)") (class "Default")
      (node (ref "C15") (pin "2") (pinfunction "2_2") (pintype "passive"))
      (node (ref "R7") (pin "1") (pinfunction "1_1") (pintype "passive"))
      (node (ref "U1") (pin "7") (pinfunction "NRST_7") (pintype "passive"))
    )
    (net (code "54") (name "Net-(U1A-PA15)") (class "Default")
      (node (ref "R4") (pin "2") (pinfunction "2_2") (pintype "passive"))
      (node (ref "U1") (pin "38") (pinfunction "PA15_38") (pintype "passive"))
    )
    (net (code "55") (name "Net-(U1A-PH0-OSC_IN)") (class "Default")
      (node (ref "C8") (pin "1") (pinfunction "1_1") (pintype "passive"))
      (node (ref "U1") (pin "5") (pinfunction "PH0-OSC_IN_5") (pintype "passive"))
      (node (ref "X1") (pin "1") (pinfunction "1_1") (pintype "passive"))
    )
    (net (code "56") (name "Net-(U1A-PH1-OSC_IN)") (class "Default")
      (node (ref "C11") (pin "1") (pinfunction "1_1") (pintype "passive"))
      (node (ref "U1") (pin "6") (pinfunction "PH1-OSC_IN_6") (pintype "passive"))
      (node (ref "X1") (pin "3") (pinfunction "3_3") (pintype "passive"))
    )
    (net (code "57") (name "Net-(U1A-VCAP1)") (class "Default")
      (node (ref "C12") (pin "1") (pinfunction "1_1") (pintype "passive"))
      (node (ref "U1") (pin "22") (pinfunction "VCAP1_22") (pintype "passive"))
    )
    (net (code "58") (name "Net-(U2-AD0)") (class "Default")
      (node (ref "R6") (pin "1") (pinfunction "1_1") (pintype "passive"))
      (node (ref "U2") (pin "9") (pinfunction "AD0_9") (pintype "passive"))
    )
    (net (code "59") (name "Net-(U2-CPOUT)") (class "Default")
      (node (ref "C1") (pin "2") (pinfunction "2_2") (pintype "passive"))
      (node (ref "U2") (pin "20") (pinfunction "CPOUT_20") (pintype "passive"))
    )
    (net (code "60") (name "Net-(U2-REGOUT)") (class "Default")
      (node (ref "C14") (pin "2") (pinfunction "2_2") (pintype "passive"))
      (node (ref "U2") (pin "10") (pinfunction "REGOUT_10") (pintype "passive"))
    )
    (net (code "61") (name "Net-(U3-ANT1)") (class "Default")
      (node (ref "L2") (pin "1") (pinfunction "1_1") (pintype "passive"))
      (node (ref "L3") (pin "1") (pinfunction "1_1") (pintype "passive"))
      (node (ref "U3") (pin "12") (pinfunction "ANT1_12") (pintype "passive"))
    )
    (net (code "62") (name "Net-(U3-ANT2)") (class "Default")
      (node (ref "L1") (pin "1") (pinfunction "1_1") (pintype "passive"))
      (node (ref "L2") (pin "2") (pinfunction "2_2") (pintype "passive"))
      (node (ref "U3") (pin "13") (pinfunction "ANT2_13") (pintype "passive"))
    )
    (net (code "63") (name "Net-(U3-IREF)") (class "Default")
      (node (ref "R3") (pin "1") (pinfunction "1_1") (pintype "passive"))
      (node (ref "U3") (pin "16") (pinfunction "IREF_16") (pintype "passive"))
    )
    (net (code "64") (name "Net-(U3-VDD_PA)") (class "Default")
      (node (ref "C10") (pin "2") (pinfunction "2_2") (pintype "passive"))
      (node (ref "C9") (pin "2") (pinfunction "2_2") (pintype "passive"))
      (node (ref "L3") (pin "2") (pinfunction "2_2") (pintype "passive"))
      (node (ref "U3") (pin "11") (pinfunction "VDD_PA_11") (pintype "passive"))
    )
    (net (code "65") (name "Net-(U3-XC1)") (class "Default")
      (node (ref "C17") (pin "2") (pinfunction "2_2") (pintype "passive"))
      (node (ref "U3") (pin "10") (pinfunction "XC1_10") (pintype "passive"))
      (node (ref "X2") (pin "3") (pinfunction "3_3") (pintype "passive"))
    )
    (net (code "66") (name "Net-(U3-XC2)") (class "Default")
      (node (ref "C16") (pin "2") (pinfunction "2_2") (pintype "passive"))
      (node (ref "U3") (pin "9") (pinfunction "XC2_9") (pintype "passive"))
      (node (ref "X2") (pin "1") (pinfunction "1_1") (pintype "passive"))
    )
    (net (code "67") (name "Net-(U4-AISEN)") (class "Default")
      (node (ref "R13") (pin "1") (pinfunction "1_1") (pintype "passive"))
      (node (ref "U4") (pin "3") (pinfunction "AISEN_3") (pintype "passive"))
    )
    (net (code "68") (name "Net-(U4-BISEN)") (class "Default")
      (node (ref "R14") (pin "1") (pinfunction "1_1") (pintype "passive"))
      (node (ref "U4") (pin "6") (pinfunction "BISEN_6") (pintype "passive"))
    )
    (net (code "69") (name "Net-(U4-VINT)") (class "Default")
      (node (ref "C22") (pin "2") (pinfunction "2_2") (pintype "passive"))
      (node (ref "U4") (pin "14") (pinfunction "VINT_14") (pintype "passive"))
    )
    (net (code "70") (name "Net-(U4-nFAULT)") (class "Default")
      (node (ref "R16") (pin "2") (pinfunction "2_2") (pintype "passive"))
      (node (ref "U4") (pin "8") (pinfunction "nFAULT_8") (pintype "passive"))
    )
    (net (code "71") (name "Net-(USB1-D+)") (class "Default")
      (node (ref "R17") (pin "1") (pinfunction "1_1") (pintype "passive"))
      (node (ref "USB1") (pin "3") (pinfunction "D+_3") (pintype "passive"))
    )
    (net (code "72") (name "Net-(USB1-D-)") (class "Default")
      (node (ref "R19") (pin "1") (pinfunction "1_1") (pintype "passive"))
      (node (ref "USB1") (pin "2") (pinfunction "D-_2") (pintype "passive"))
    )
    (net (code "73") (name "Net-(Y1-FP)") (class "Default")
      (node (ref "C5") (pin "2") (pinfunction "2_2") (pintype "passive"))
      (node (ref "C6") (pin "2") (pinfunction "2_2") (pintype "passive"))
      (node (ref "Y1") (pin "1") (pinfunction "FP_1") (pintype "passive"))
    )
    (net (code "74") (name "RF_3V3") (class "Default")
      (node (ref "C2") (pin "1") (pinfunction "1_1") (pintype "passive"))
      (node (ref "C3") (pin "1") (pinfunction "1_1") (pintype "passive"))
      (node (ref "C4") (pin "1") (pinfunction "1_1") (pintype "passive"))
      (node (ref "R9") (pin "2") (pinfunction "2_2") (pintype "passive"))
      (node (ref "U3") (pin "15") (pinfunction "VDD_15") (pintype "passive"))
      (node (ref "U3") (pin "18") (pinfunction "VDD_18") (pintype "passive"))
      (node (ref "U3") (pin "19") (pinfunction "DVDD_19") (pintype "passive"))
      (node (ref "U3") (pin "7") (pinfunction "VDD_7") (pintype "passive"))
    )
    (net (code "75") (name "RF_GND") (class "Default")
      (node (ref "C10") (pin "1") (pinfunction "1_1") (pintype "passive"))
      (node (ref "C16") (pin "1") (pinfunction "1_1") (pintype "passive"))
      (node (ref "C17") (pin "1") (pinfunction "1_1") (pintype "passive"))
      (node (ref "C2") (pin "2") (pinfunction "2_2") (pintype "passive"))
      (node (ref "C3") (pin "2") (pinfunction "2_2") (pintype "passive"))
      (node (ref "C4") (pin "2") (pinfunction "2_2") (pintype "passive"))
      (node (ref "C6") (pin "1") (pinfunction "1_1") (pintype "passive"))
      (node (ref "C9") (pin "1") (pinfunction "1_1") (pintype "passive"))
      (node (ref "R3") (pin "2") (pinfunction "2_2") (pintype "passive"))
      (node (ref "R8") (pin "2") (pinfunction "2_2") (pintype "passive"))
      (node (ref "U3") (pin "14") (pinfunction "VSS_14") (pintype "passive"))
      (node (ref "U3") (pin "17") (pinfunction "VSS_17") (pintype "passive"))
      (node (ref "U3") (pin "20") (pinfunction "VSS_20") (pintype "passive"))
      (node (ref "U3") (pin "8") (pinfunction "VSS_8") (pintype "passive"))
      (node (ref "X2") (pin "2") (pinfunction "2_2") (pintype "passive"))
      (node (ref "X2") (pin "4") (pinfunction "4_4") (pintype "passive"))
    )
    (net (code "76") (name "V3.3") (class "Default")
      (node (ref "C13") (pin "2") (pinfunction "2_2") (pintype "passive"))
      (node (ref "C18") (pin "2") (pinfunction "2_2") (pintype "passive"))
      (node (ref "C19") (pin "2") (pinfunction "2_2") (pintype "passive"))
      (node (ref "C20") (pin "2") (pinfunction "2_2") (pintype "passive"))
      (node (ref "C21") (pin "2") (pinfunction "2_2") (pintype "passive"))
      (node (ref "C26") (pin "2") (pinfunction "2_2") (pintype "passive"))
      (node (ref "C7") (pin "1") (pinfunction "1_1") (pintype "passive"))
      (node (ref "JP1") (pin "6") (pinfunction "6_6") (pintype "passive"))
      (node (ref "JP2") (pin "2") (pinfunction "2_2") (pintype "passive"))
      (node (ref "JP3") (pin "4") (pinfunction "4_4") (pintype "passive"))
      (node (ref "JP4") (pin "2") (pinfunction "2_2") (pintype "passive"))
      (node (ref "JP5") (pin "2") (pinfunction "2_2") (pintype "passive"))
      (node (ref "M1") (pin "1") (pinfunction "VCC_1") (pintype "passive"))
      (node (ref "R1") (pin "2") (pinfunction "2_2") (pintype "passive"))
      (node (ref "R10") (pin "1") (pinfunction "1_1") (pintype "passive"))
      (node (ref "R12") (pin "2") (pinfunction "2_2") (pintype "passive"))
      (node (ref "R16") (pin "1") (pinfunction "1_1") (pintype "passive"))
      (node (ref "R2") (pin "2") (pinfunction "2_2") (pintype "passive"))
      (node (ref "R7") (pin "2") (pinfunction "2_2") (pintype "passive"))
      (node (ref "R9") (pin "1") (pinfunction "1_1") (pintype "passive"))
      (node (ref "U1") (pin "1") (pinfunction "VBAT_1") (pintype "passive"))
      (node (ref "U1") (pin "24") (pinfunction "VDD_24") (pintype "passive"))
      (node (ref "U1") (pin "36") (pinfunction "VDD_36") (pintype "passive"))
      (node (ref "U1") (pin "48") (pinfunction "VDD_48") (pintype "passive"))
      (node (ref "U1") (pin "9") (pinfunction "VDDA/VREF+_9") (pintype "passive"))
      (node (ref "U2") (pin "13") (pinfunction "VDD_13") (pintype "passive"))
      (node (ref "U2") (pin "8") (pinfunction "VLOGIC_8") (pintype "passive"))
      (node (ref "V1") (pin "2") (pinfunction "Vout_2") (pintype "passive"))
    )
    (net (code "77") (name "VBAT") (class "Default")
      (node (ref "C29") (pin "2") (pinfunction "2_2") (pintype "passive"))
      (node (ref "IC1") (pin "4") (pinfunction "EN_4") (pintype "passive"))
      (node (ref "IC1") (pin "5") (pinfunction "VCC_5") (pintype "passive"))
      (node (ref "L4") (pin "2") (pinfunction "2_2") (pintype "passive"))
      (node (ref "R18") (pin "2") (pinfunction "2_2") (pintype "passive"))
      (node (ref "S1") (pin "2") (pinfunction "2_2") (pintype "passive"))
    )
    (net (code "78") (name "VCC") (class "Default")
      (node (ref "C24") (pin "2") (pinfunction "2_2") (pintype "passive"))
      (node (ref "IC2") (pin "4") (pinfunction "VCC_4") (pintype "passive"))
      (node (ref "IC2") (pin "8") (pinfunction "CE_8") (pintype "passive"))
      (node (ref "LED4") (pin "1") (pinfunction "A_1") (pintype "passive"))
      (node (ref "LED5") (pin "1") (pinfunction "A_1") (pintype "passive"))
      (node (ref "USB1") (pin "1") (pinfunction "+5V_1") (pintype "passive"))
    )
    (net (code "79") (name "unconnected-(IC1-NC-Pad6)") (class "Default")
      (node (ref "IC1") (pin "6") (pinfunction "NC_6") (pintype "passive"))
    )
    (net (code "80") (name "unconnected-(M1-KEY-Pad21)") (class "Default")
      (node (ref "M1") (pin "21") (pinfunction "KEY_21") (pintype "passive"))
    )
    (net (code "81") (name "unconnected-(M1-P06{slash}PWM4-Pad16)") (class "Default")
      (node (ref "M1") (pin "16") (pinfunction "P06/PWM4_16") (pintype "passive"))
    )
    (net (code "82") (name "unconnected-(M1-P07{slash}PWM3-Pad15)") (class "Default")
      (node (ref "M1") (pin "15") (pinfunction "P07/PWM3_15") (pintype "passive"))
    )
    (net (code "83") (name "unconnected-(M1-P10{slash}PWM1-Pad14)") (class "Default")
      (node (ref "M1") (pin "14") (pinfunction "P10/PWM1_14") (pintype "passive"))
    )
    (net (code "84") (name "unconnected-(M1-P11{slash}PWM2-Pad7)") (class "Default")
      (node (ref "M1") (pin "7") (pinfunction "P11/PWM2_7") (pintype "passive"))
    )
    (net (code "85") (name "unconnected-(M1-P12{slash}IO1-Pad8)") (class "Default")
      (node (ref "M1") (pin "8") (pinfunction "P12/IO1_8") (pintype "passive"))
    )
    (net (code "86") (name "unconnected-(M1-P13{slash}IO2-Pad9)") (class "Default")
      (node (ref "M1") (pin "9") (pinfunction "P13/IO2_9") (pintype "passive"))
    )
    (net (code "87") (name "unconnected-(M1-P14{slash}IO4-Pad13)") (class "Default")
      (node (ref "M1") (pin "13") (pinfunction "P14/IO4_13") (pintype "passive"))
    )
    (net (code "88") (name "unconnected-(M1-P15{slash}IO3-Pad10)") (class "Default")
      (node (ref "M1") (pin "10") (pinfunction "P15/IO3_10") (pintype "passive"))
    )
    (net (code "89") (name "unconnected-(M1-P17-Pad5)") (class "Default")
      (node (ref "M1") (pin "5") (pinfunction "P17_5") (pintype "passive"))
    )
    (net (code "90") (name "unconnected-(M1-P20-Pad4)") (class "Default")
      (node (ref "M1") (pin "4") (pinfunction "P20_4") (pintype "passive"))
    )
    (net (code "91") (name "unconnected-(M1-P21-Pad3)") (class "Default")
      (node (ref "M1") (pin "3") (pinfunction "P21_3") (pintype "passive"))
    )
    (net (code "92") (name "unconnected-(M1-P22-Pad2)") (class "Default")
      (node (ref "M1") (pin "2") (pinfunction "P22_2") (pintype "passive"))
    )
    (net (code "93") (name "unconnected-(M1-PWRC-Pad22)") (class "Default")
      (node (ref "M1") (pin "22") (pinfunction "PWRC_22") (pintype "passive"))
    )
    (net (code "94") (name "unconnected-(M1-RST-Pad23)") (class "Default")
      (node (ref "M1") (pin "23") (pinfunction "RST_23") (pintype "passive"))
    )
    (net (code "95") (name "unconnected-(M1-RTC1-Pad17)") (class "Default")
      (node (ref "M1") (pin "17") (pinfunction "RTC1_17") (pintype "passive"))
    )
    (net (code "96") (name "unconnected-(M1-RTC2-Pad18)") (class "Default")
      (node (ref "M1") (pin "18") (pinfunction "RTC2_18") (pintype "passive"))
    )
    (net (code "97") (name "unconnected-(M1-SCK-Pad11)") (class "Default")
      (node (ref "M1") (pin "11") (pinfunction "SCK_11") (pintype "passive"))
    )
    (net (code "98") (name "unconnected-(M1-SDA-Pad12)") (class "Default")
      (node (ref "M1") (pin "12") (pinfunction "SDA_12") (pintype "passive"))
    )
    (net (code "99") (name "unconnected-(S1-Pad3)") (class "Default")
      (node (ref "S1") (pin "3") (pinfunction "3_3") (pintype "passive"))
    )
    (net (code "100") (name "unconnected-(U1A-PC14-OSC32_IN-Pad3)") (class "Default")
      (node (ref "U1") (pin "3") (pinfunction "PC14-OSC32_IN_3") (pintype "passive+no_connect"))
    )
    (net (code "101") (name "unconnected-(U1A-PC15-OSC32_OUT-Pad4)") (class "Default")
      (node (ref "U1") (pin "4") (pinfunction "PC15-OSC32_OUT_4") (pintype "passive+no_connect"))
    )
    (net (code "102") (name "unconnected-(U2-A-CL-Pad7)") (class "Default")
      (node (ref "U2") (pin "7") (pinfunction "A-CL_7") (pintype "passive+no_connect"))
    )
    (net (code "103") (name "unconnected-(U2-A_DA-Pad6)") (class "Default")
      (node (ref "U2") (pin "6") (pinfunction "A_DA_6") (pintype "passive+no_connect"))
    )
    (net (code "104") (name "unconnected-(U2-CLKOUT-Pad22)") (class "Default")
      (node (ref "U2") (pin "22") (pinfunction "CLKOUT_22") (pintype "passive+no_connect"))
    )
    (net (code "105") (name "unconnected-(U2-NC-Pad2)") (class "Default")
      (node (ref "U2") (pin "2") (pinfunction "NC_2") (pintype "passive+no_connect"))
    )
    (net (code "106") (name "unconnected-(U2-NC-Pad3)") (class "Default")
      (node (ref "U2") (pin "3") (pinfunction "NC_3") (pintype "passive+no_connect"))
    )
    (net (code "107") (name "unconnected-(U2-NC-Pad4)") (class "Default")
      (node (ref "U2") (pin "4") (pinfunction "NC_4") (pintype "passive+no_connect"))
    )
    (net (code "108") (name "unconnected-(U2-NC-Pad5)") (class "Default")
      (node (ref "U2") (pin "5") (pinfunction "NC_5") (pintype "passive+no_connect"))
    )
    (net (code "109") (name "unconnected-(U2-NC-Pad14)") (class "Default")
      (node (ref "U2") (pin "14") (pinfunction "NC_14") (pintype "passive+no_connect"))
    )
    (net (code "110") (name "unconnected-(U2-NC-Pad15)") (class "Default")
      (node (ref "U2") (pin "15") (pinfunction "NC_15") (pintype "passive+no_connect"))
    )
    (net (code "111") (name "unconnected-(U2-NC-Pad16)") (class "Default")
      (node (ref "U2") (pin "16") (pinfunction "NC_16") (pintype "passive+no_connect"))
    )
    (net (code "112") (name "unconnected-(U2-NC-Pad17)") (class "Default")
      (node (ref "U2") (pin "17") (pinfunction "NC_17") (pintype "passive+no_connect"))
    )
    (net (code "113") (name "unconnected-(U2-RESV-Pad19)") (class "Default")
      (node (ref "U2") (pin "19") (pinfunction "RESV_19") (pintype "passive+no_connect"))
    )
    (net (code "114") (name "unconnected-(U2-RESV-Pad21)") (class "Default")
      (node (ref "U2") (pin "21") (pinfunction "RESV_21") (pintype "passive+no_connect"))
    )
    (net (code "115") (name "unconnected-(U4-NC-Pad11)") (class "Default")
      (node (ref "U4") (pin "11") (pinfunction "NC_11") (pintype "passive+no_connect"))
    )
    (net (code "116") (name "unconnected-(USB1-ID-Pad4)") (class "Default")
      (node (ref "USB1") (pin "4") (pinfunction "ID_4") (pintype "passive+no_connect"))
    )
    (net (code "117") (name "unconnected-(Y1-NC-Pad2)") (class "Default")
      (node (ref "Y1") (pin "2") (pinfunction "NC_2") (pintype "passive+no_connect"))
    )
  )
)
